# external_battery_charger.net
KiCad netlist of a schematic drawn in Altium Designer
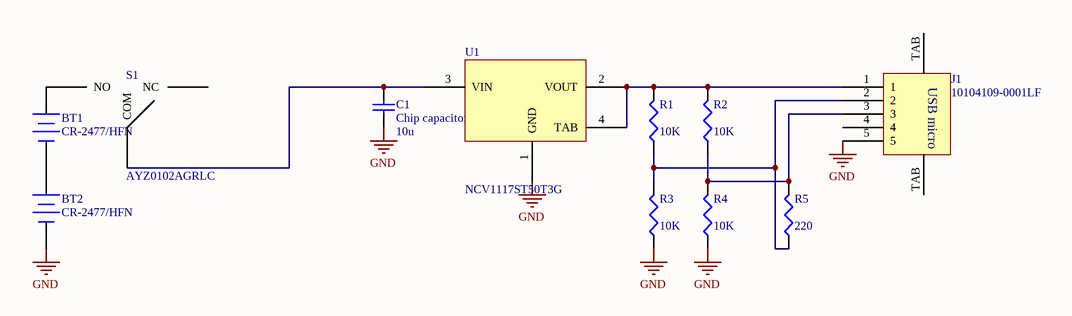
[diagram p0: external battery charger (w button) main board.SchDoc]

(export (version "E")
  (design (tool "Eeschema 10.0.6"))
  (components
    (comp (ref "BT1")
      (value "CR-2477/HFN")
      (footprint "PCBComponent_1")
      (description "CR2477 battery with throughhole contacts")
      (fields (field (name "PUBLISHER") "Altium Limited"))
      (libsource (lib "Miscellaneous Devices") (part "Battery"))
    )
    (comp (ref "BT2")
      (value "CR-2477/HFN")
      (footprint "PCBComponent_1")
      (description "CR2477 battery with throughhole contacts")
      (fields (field (name "PUBLISHER") "Altium Limited"))
      (libsource (lib "Miscellaneous Devices") (part "Battery"))
    )
    (comp (ref "C1")
      (value "Chip capacitor 0603")
      (footprint "RESC1608M")
      (description "Capacitor 10uF")
      (fields (field (name "ALTIUM_VALUE") "10u") (field (name "PUBLISHER") "Altium Limited"))
      (libsource (lib "Miscellaneous Devices") (part "Cap Semi"))
    )
    (comp (ref "J1")
      (value "10104109-0001LF")
      (footprint "usb-microB-plug")
      (description "Micro USB plug, 5pin")
      (libsource (lib "USB conn type B micro Plug") (part "USB micro"))
    )
    (comp (ref "R1")
      (value "10K")
      (footprint "RESC1608M")
      (description "Resistor 10k")
      (fields (field (name "Comment") "Chip resistor 0603") (field (name "PUBLISHER") "Altium Limited"))
      (libsource (lib "Miscellaneous Devices") (part "Res3"))
    )
    (comp (ref "R2")
      (value "10K")
      (footprint "RESC1608M")
      (description "Resistor 10k")
      (fields (field (name "Comment") "Chip resistor 0603") (field (name "PUBLISHER") "Altium Limited"))
      (libsource (lib "Miscellaneous Devices") (part "Res3"))
    )
    (comp (ref "R3")
      (value "10K")
      (footprint "RESC1608M")
      (description "Resistor 10k")
      (fields (field (name "Comment") "Chip resistor 0603") (field (name "PUBLISHER") "Altium Limited"))
      (libsource (lib "Miscellaneous Devices") (part "Res3"))
    )
    (comp (ref "R4")
      (value "10K")
      (footprint "RESC1608M")
      (description "Resistor 10k")
      (fields (field (name "Comment") "Chip resistor 0603") (field (name "PUBLISHER") "Altium Limited"))
      (libsource (lib "Miscellaneous Devices") (part "Res3"))
    )
    (comp (ref "R5")
      (value "220")
      (footprint "RESC1608M")
      (description "Resistor 220 Ohm")
      (fields (field (name "Comment") "Chip resistor 0603") (field (name "PUBLISHER") "Altium Limited"))
      (libsource (lib "Miscellaneous Devices") (part "Res3"))
    )
    (comp (ref "S1")
      (value "AYZ0102AGRLC")
      (footprint "SPDT SWITCH SMD")
      (description "Switch Slide SPDT SMD")
      (libsource (lib "Switches") (part "SPDT switch"))
    )
    (comp (ref "U1")
      (value "NCV1117ST50T3G")
      (footprint "SOT223-4M")
      (description "Voltage Regulator LDO 5V SOT223")
      (libsource (lib "AP1117") (part "Component_1"))
    )
  )
  (nets
    (net (code "1") (name "GND") (class "Default")
      (node (ref "BT2") (pin "2") (pinfunction "-_2") (pintype "passive"))
      (node (ref "C1") (pin "1") (pinfunction "1_1") (pintype "passive"))
      (node (ref "J1") (pin "5") (pinfunction "5_5") (pintype "passive"))
      (node (ref "R3") (pin "1") (pinfunction "1_1") (pintype "passive"))
      (node (ref "R4") (pin "1") (pinfunction "1_1") (pintype "passive"))
      (node (ref "U1") (pin "1") (pinfunction "GND_1") (pintype "passive"))
    )
    (net (code "2") (name "Net-(BT1-+)") (class "Default")
      (node (ref "BT1") (pin "1") (pinfunction "+_1") (pintype "passive"))
      (node (ref "S1") (pin "1") (pinfunction "NO_1") (pintype "passive"))
    )
    (net (code "3") (name "Net-(BT1--)") (class "Default")
      (node (ref "BT1") (pin "2") (pinfunction "-_2") (pintype "passive"))
      (node (ref "BT2") (pin "1") (pinfunction "+_1") (pintype "passive"))
    )
    (net (code "4") (name "Net-(J1-Pad2)") (class "Default")
      (node (ref "J1") (pin "2") (pinfunction "2_2") (pintype "passive"))
      (node (ref "R1") (pin "1") (pinfunction "1_1") (pintype "passive"))
      (node (ref "R3") (pin "2") (pinfunction "2_2") (pintype "passive"))
      (node (ref "R5") (pin "1") (pinfunction "1_1") (pintype "passive"))
    )
    (net (code "5") (name "Net-(J1-Pad3)") (class "Default")
      (node (ref "J1") (pin "3") (pinfunction "3_3") (pintype "passive"))
      (node (ref "R2") (pin "1") (pinfunction "1_1") (pintype "passive"))
      (node (ref "R4") (pin "2") (pinfunction "2_2") (pintype "passive"))
      (node (ref "R5") (pin "2") (pinfunction "2_2") (pintype "passive"))
    )
    (net (code "6") (name "Net-(S1-COM)") (class "Default")
      (node (ref "C1") (pin "2") (pinfunction "2_2") (pintype "passive"))
      (node (ref "S1") (pin "2") (pinfunction "COM_2") (pintype "passive"))
      (node (ref "U1") (pin "3") (pinfunction "VIN_3") (pintype "passive"))
    )
    (net (code "7") (name "Net-(U1-TAB)") (class "Default")
      (node (ref "J1") (pin "1") (pinfunction "1_1") (pintype "passive"))
      (node (ref "R1") (pin "2") (pinfunction "2_2") (pintype "passive"))
      (node (ref "R2") (pin "2") (pinfunction "2_2") (pintype "passive"))
      (node (ref "U1") (pin "2") (pinfunction "VOUT_2") (pintype "passive"))
      (node (ref "U1") (pin "4") (pinfunction "TAB_4") (pintype "passive"))
    )
    (net (code "8") (name "unconnected-(J1-Pad4)") (class "Default")
      (node (ref "J1") (pin "4") (pinfunction "4_4") (pintype "passive"))
    )
    (net (code "9") (name "unconnected-(J1-tab-PadTAB)") (class "Default")
      (node (ref "J1") (pin "TAB") (pinfunction "tab_TAB") (pintype "passive"))
    )
    (net (code "10") (name "unconnected-(J1-tab-PadTAB)_1") (class "Default")
      (node (ref "J1") (pin "TAB") (pinfunction "tab_TAB") (pintype "passive"))
    )
    (net (code "11") (name "unconnected-(S1-NC-Pad3)") (class "Default")
      (node (ref "S1") (pin "3") (pinfunction "NC_3") (pintype "passive"))
    )
  )
)
